# LurkerNanov12.net
KiCad netlist of a schematic drawn in EAGLE
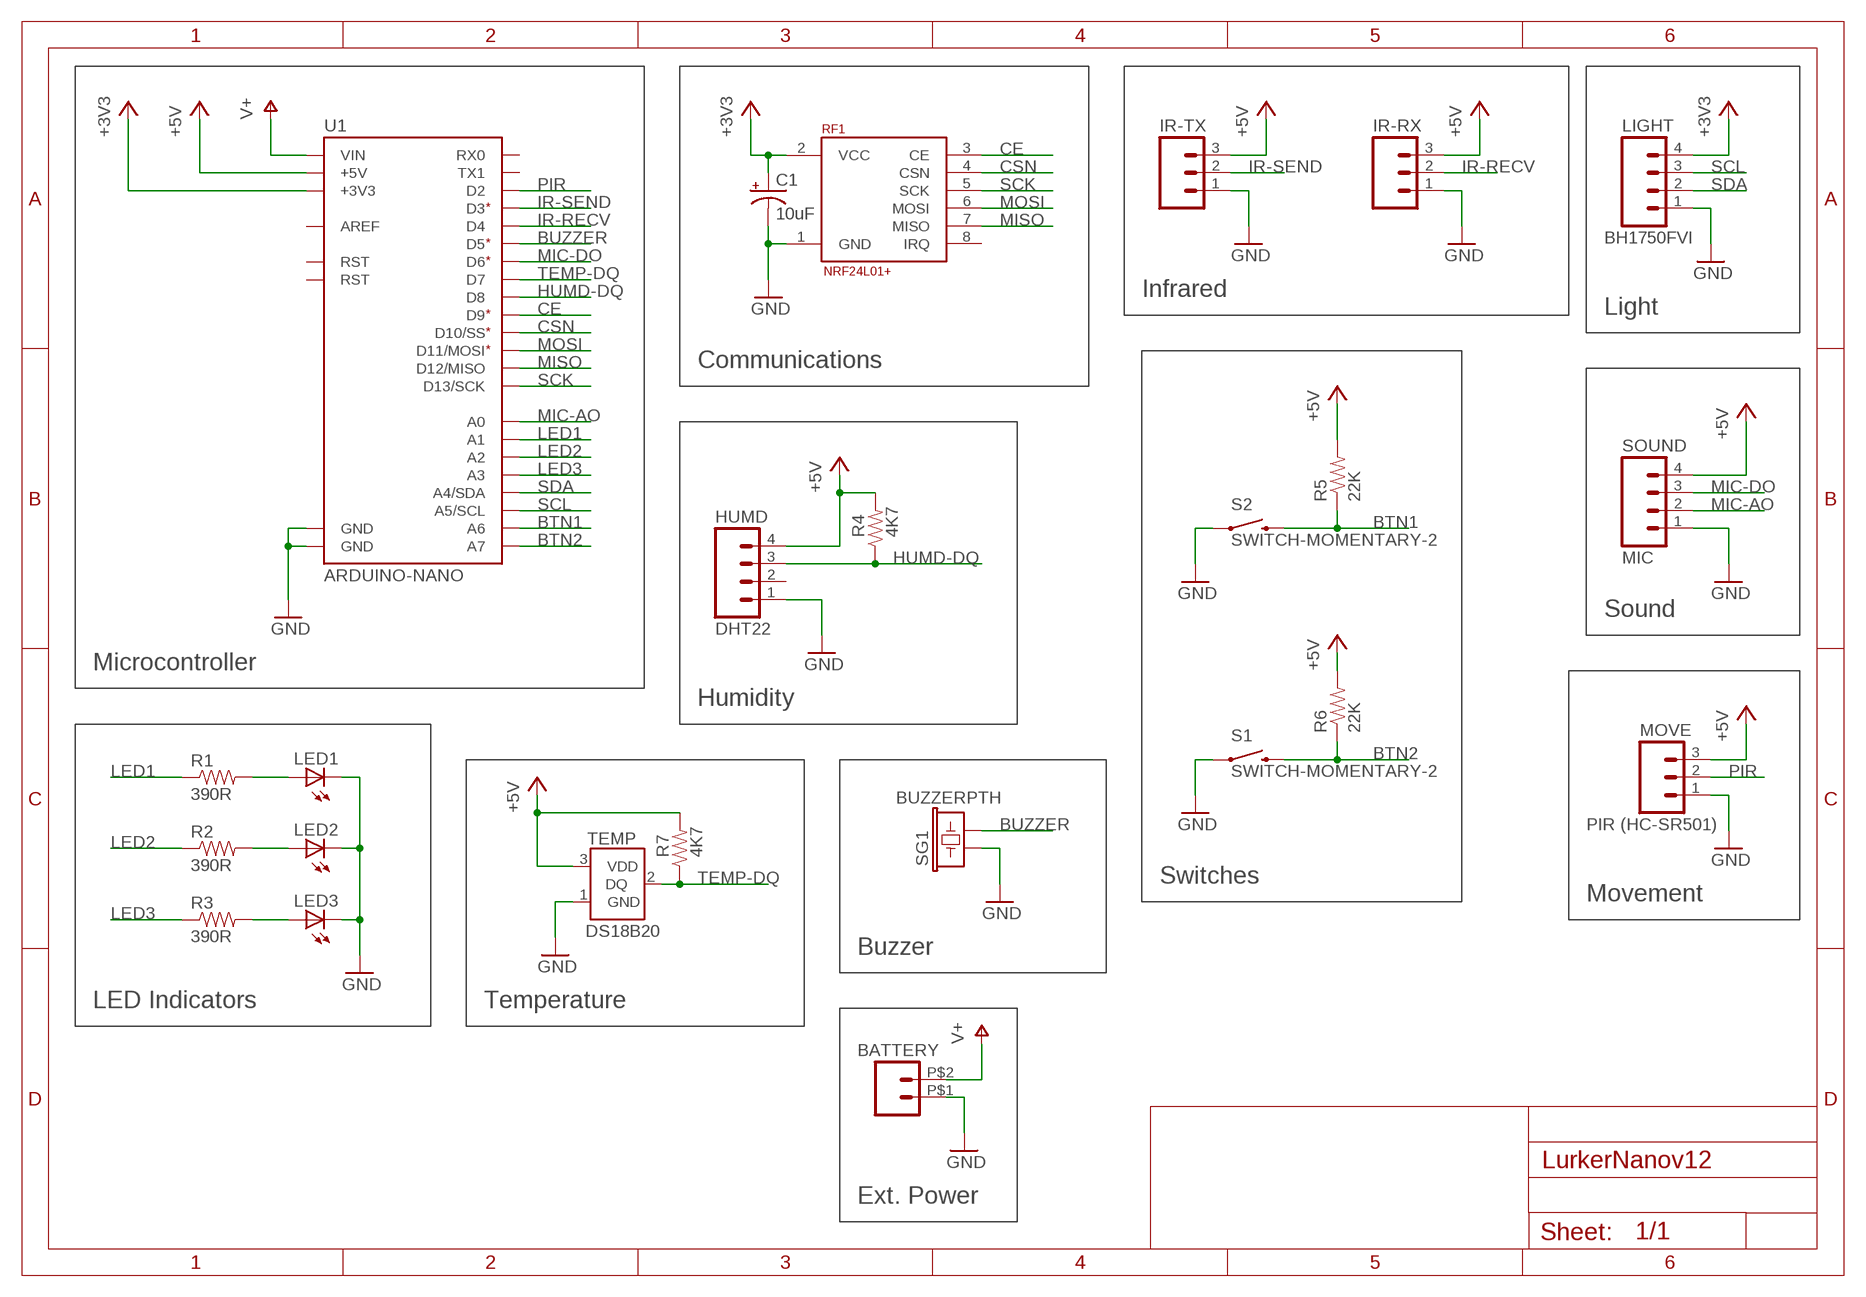
[diagram p0: schematic, sheet 1, part 1 of 2]
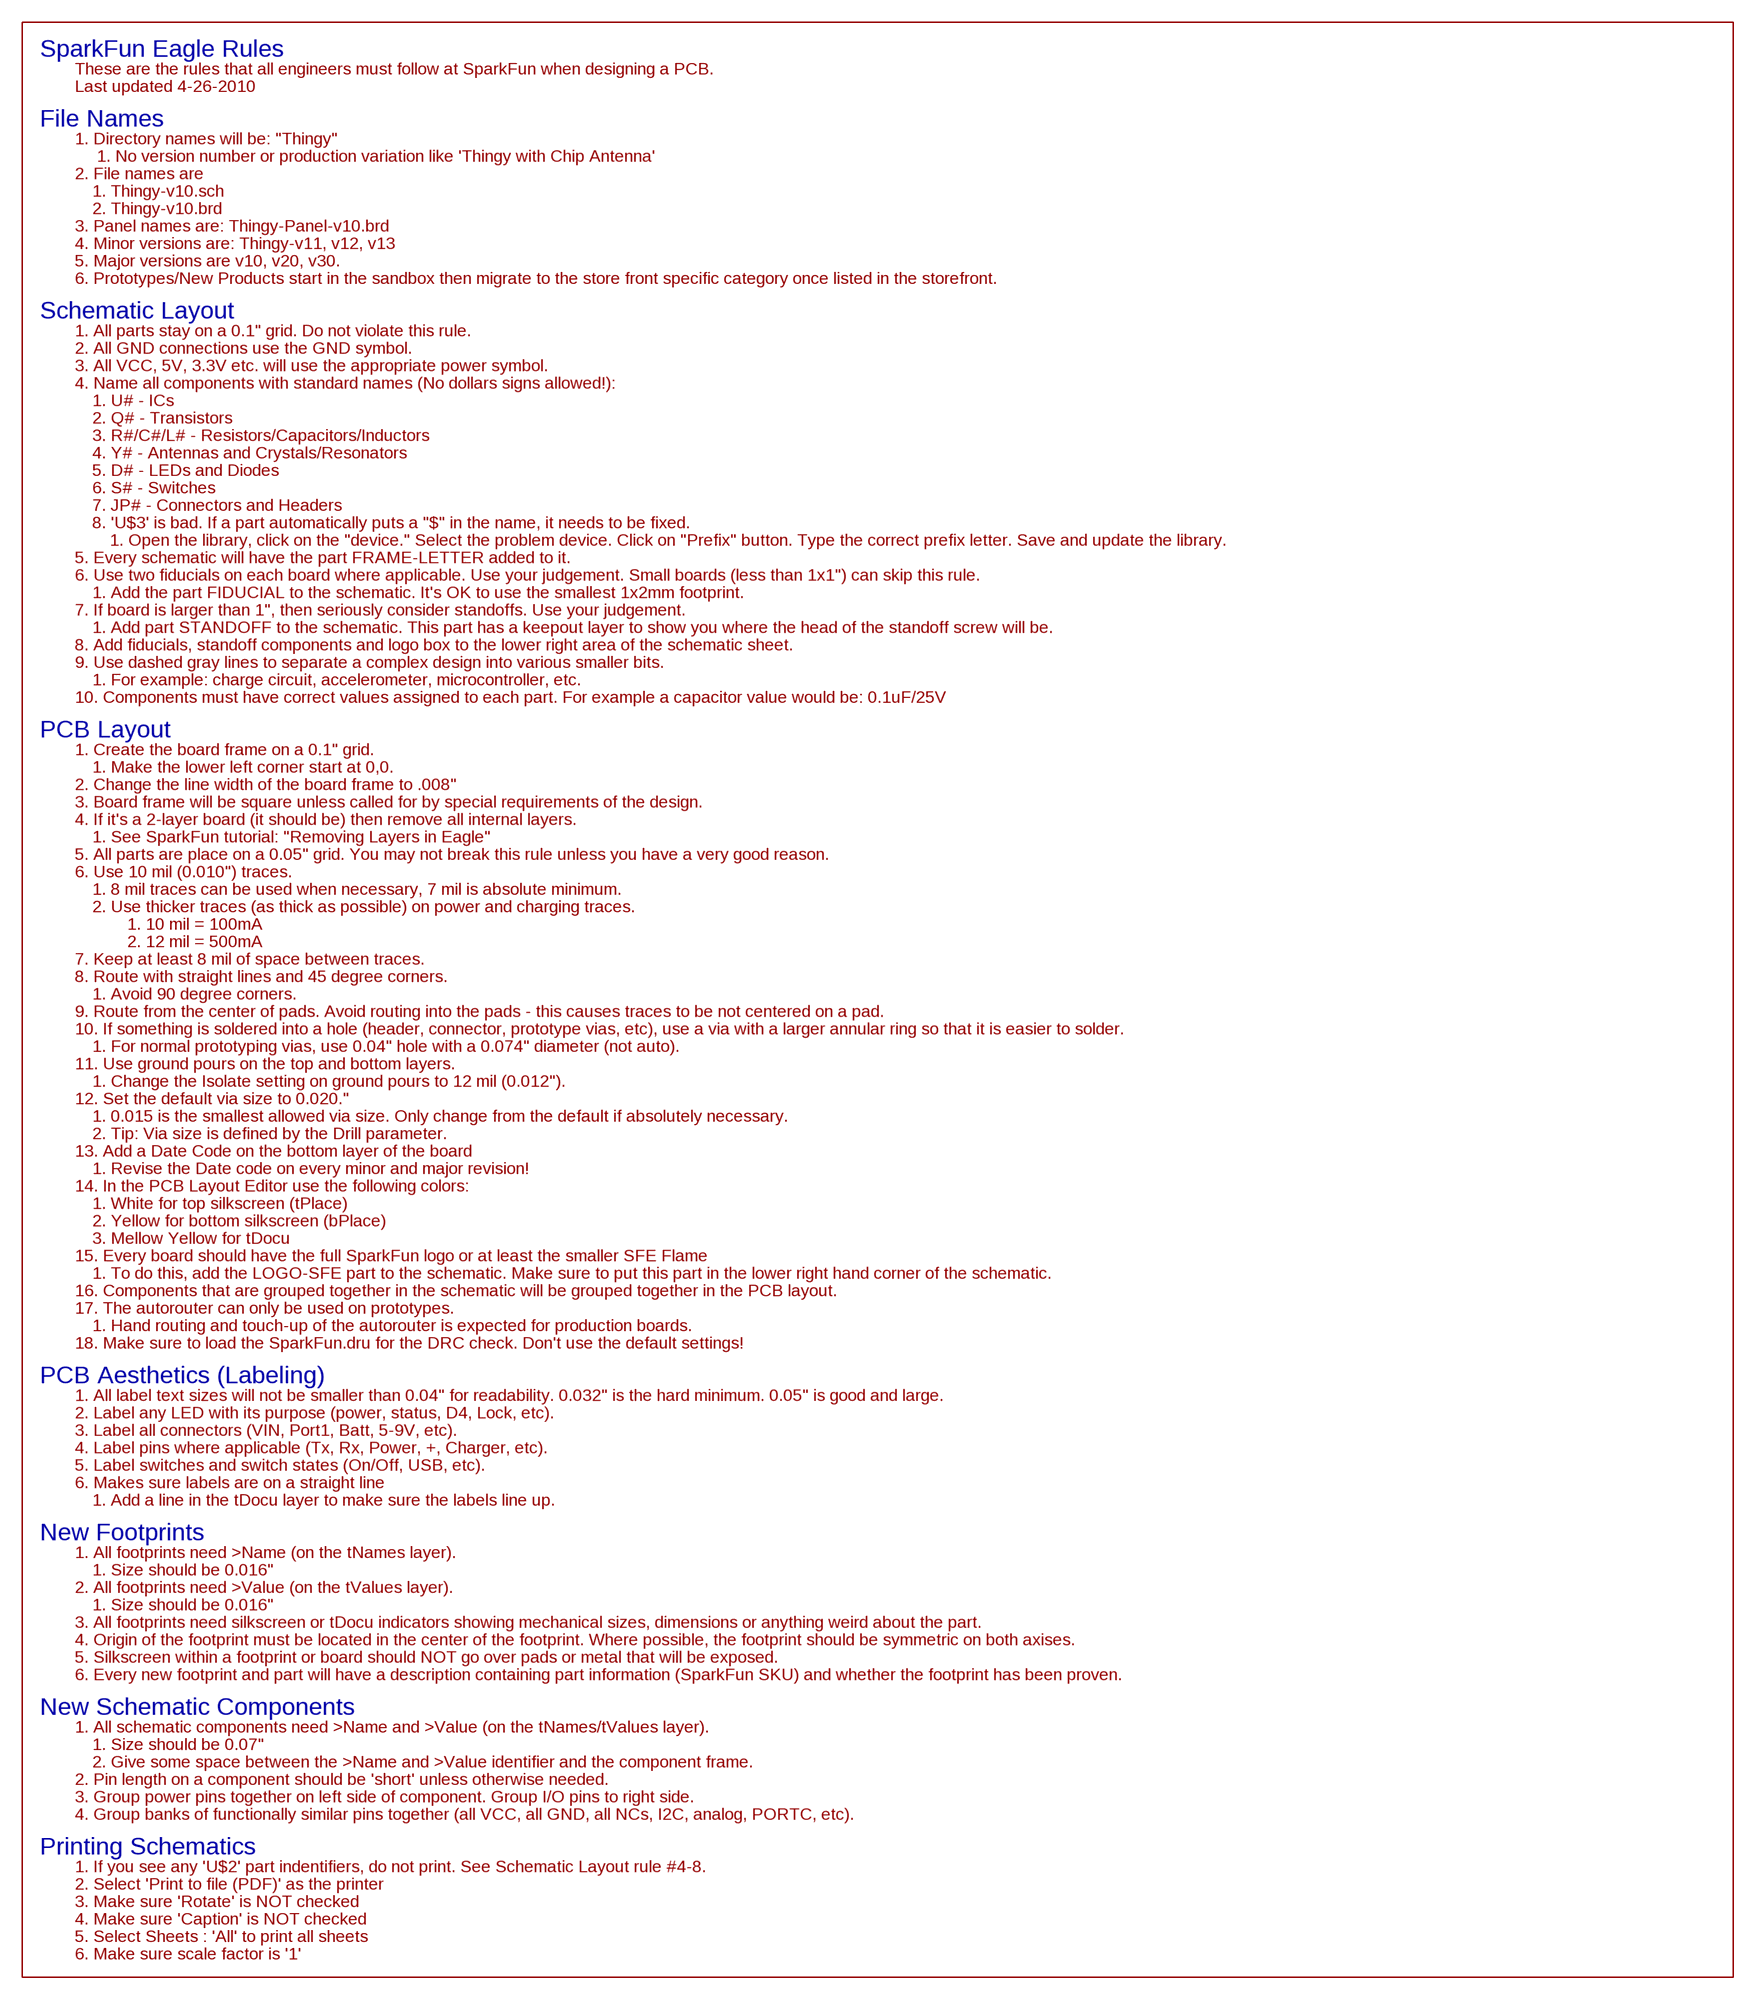
[diagram p1: schematic, sheet 1, part 2 of 2]

(export (version "E")
  (design (tool "Eeschema 10.0.6"))
  (components
    (comp (ref "BATTERY")
      (value "M02PTH2")
      (footprint "eagle-import:1X02_BIG")
      (libsource (lib "eagle-import") (part "M02PTH2"))
    )
    (comp (ref "C1")
      (value "10uF")
      (footprint "eagle-import:EIA3216")
      (libsource (lib "eagle-import") (part "CAP_POL1206"))
    )
    (comp (ref "HUMD")
      (value "DHT22")
      (footprint "eagle-import:1X04")
      (libsource (lib "eagle-import") (part "M04PTH"))
    )
    (comp (ref "IR-RX")
      (value "M03PTH")
      (footprint "eagle-import:1X03")
      (libsource (lib "eagle-import") (part "M03PTH"))
    )
    (comp (ref "IR-TX")
      (value "M03PTH")
      (footprint "eagle-import:1X03")
      (libsource (lib "eagle-import") (part "M03PTH"))
    )
    (comp (ref "LED1")
      (value "LED1206")
      (footprint "eagle-import:LED-1206")
      (libsource (lib "eagle-import") (part "LED1206"))
    )
    (comp (ref "LED2")
      (value "LED1206")
      (footprint "eagle-import:LED-1206")
      (libsource (lib "eagle-import") (part "LED1206"))
    )
    (comp (ref "LED3")
      (value "LED1206")
      (footprint "eagle-import:LED-1206")
      (libsource (lib "eagle-import") (part "LED1206"))
    )
    (comp (ref "LIGHT")
      (value "BH1750FVI")
      (footprint "eagle-import:1X04")
      (libsource (lib "eagle-import") (part "M04PTH"))
    )
    (comp (ref "MOVE")
      (value "PIR (HC-SR501)")
      (footprint "eagle-import:1X03")
      (libsource (lib "eagle-import") (part "M03PTH"))
    )
    (comp (ref "R1")
      (value "390R")
      (footprint "eagle-import:1206")
      (libsource (lib "eagle-import") (part "RESISTOR1206"))
    )
    (comp (ref "R2")
      (value "390R")
      (footprint "eagle-import:1206")
      (libsource (lib "eagle-import") (part "RESISTOR1206"))
    )
    (comp (ref "R3")
      (value "390R")
      (footprint "eagle-import:1206")
      (libsource (lib "eagle-import") (part "RESISTOR1206"))
    )
    (comp (ref "R4")
      (value "4K7")
      (footprint "eagle-import:1206")
      (libsource (lib "eagle-import") (part "RESISTOR1206"))
    )
    (comp (ref "R5")
      (value "22K")
      (footprint "eagle-import:1206")
      (libsource (lib "eagle-import") (part "RESISTOR1206"))
    )
    (comp (ref "R6")
      (value "22K")
      (footprint "eagle-import:1206")
      (libsource (lib "eagle-import") (part "RESISTOR1206"))
    )
    (comp (ref "R7")
      (value "4K7")
      (footprint "eagle-import:1206")
      (libsource (lib "eagle-import") (part "RESISTOR1206"))
    )
    (comp (ref "RF1")
      (value "NRF24L01+")
      (footprint "eagle-import:NRF24L01+-HEADER")
      (libsource (lib "eagle-import") (part "NRF24L01+"))
    )
    (comp (ref "S1")
      (value "SWITCH-MOMENTARY-2")
      (footprint "eagle-import:TACTILE_SWITCH_TALL")
      (libsource (lib "eagle-import") (part "SWITCH-MOMENTARY-2"))
    )
    (comp (ref "S2")
      (value "SWITCH-MOMENTARY-2")
      (footprint "eagle-import:TACTILE_SWITCH_TALL")
      (libsource (lib "eagle-import") (part "SWITCH-MOMENTARY-2"))
    )
    (comp (ref "SG1")
      (value "BUZZERPTH")
      (footprint "eagle-import:BUZZER-12MM")
      (libsource (lib "eagle-import") (part "BUZZERPTH"))
    )
    (comp (ref "SOUND")
      (value "MIC")
      (footprint "eagle-import:1X04")
      (libsource (lib "eagle-import") (part "M04PTH"))
    )
    (comp (ref "TEMP")
      (value "DS18B20")
      (footprint "eagle-import:TO-92-AMMO")
      (libsource (lib "eagle-import") (part "DS18B20"))
    )
    (comp (ref "U1")
      (value "ARDUINO-NANO")
      (footprint "eagle-import:NANO-SHIELD")
      (libsource (lib "eagle-import") (part "ARDUINO-NANO"))
    )
  )
  (nets
    (net (code "1") (name "+3V3") (class "Default")
      (node (ref "C1") (pin "A") (pinfunction "+_A") (pintype "passive"))
      (node (ref "LIGHT") (pin "4") (pinfunction "4_4") (pintype "passive"))
      (node (ref "RF1") (pin "2") (pinfunction "VCC_2") (pintype "power_in"))
      (node (ref "U1") (pin "3V3") (pinfunction "+3V3_3V3") (pintype "power_in"))
    )
    (net (code "2") (name "+5V") (class "Default")
      (node (ref "HUMD") (pin "4") (pinfunction "4_4") (pintype "passive"))
      (node (ref "IR-RX") (pin "3") (pinfunction "3_3") (pintype "passive"))
      (node (ref "IR-TX") (pin "3") (pinfunction "3_3") (pintype "passive"))
      (node (ref "MOVE") (pin "3") (pinfunction "3_3") (pintype "passive"))
      (node (ref "R4") (pin "2") (pinfunction "2_2") (pintype "passive"))
      (node (ref "R5") (pin "2") (pinfunction "2_2") (pintype "passive"))
      (node (ref "R6") (pin "2") (pinfunction "2_2") (pintype "passive"))
      (node (ref "R7") (pin "2") (pinfunction "2_2") (pintype "passive"))
      (node (ref "SOUND") (pin "4") (pinfunction "4_4") (pintype "passive"))
      (node (ref "TEMP") (pin "3") (pinfunction "VDD_3") (pintype "power_in"))
      (node (ref "U1") (pin "5V") (pinfunction "+5V_5V") (pintype "power_in"))
    )
    (net (code "3") (name "/BTN1") (class "Default")
      (node (ref "R5") (pin "1") (pinfunction "1_1") (pintype "passive"))
      (node (ref "S2") (pin "B2") (pinfunction "2_B2") (pintype "passive"))
      (node (ref "U1") (pin "A6") (pinfunction "A6_A6") (pintype "bidirectional"))
    )
    (net (code "4") (name "/BTN2") (class "Default")
      (node (ref "R6") (pin "1") (pinfunction "1_1") (pintype "passive"))
      (node (ref "S1") (pin "B2") (pinfunction "2_B2") (pintype "passive"))
      (node (ref "U1") (pin "A7") (pinfunction "A7_A7") (pintype "bidirectional"))
    )
    (net (code "5") (name "/BUZZER") (class "Default")
      (node (ref "SG1") (pin "-") (pinfunction "2_-") (pintype "passive"))
      (node (ref "U1") (pin "D5") (pinfunction "D5_D5") (pintype "bidirectional"))
    )
    (net (code "6") (name "/CE") (class "Default")
      (node (ref "RF1") (pin "3") (pinfunction "CE_3") (pintype "bidirectional"))
      (node (ref "U1") (pin "D9") (pinfunction "D9_D9") (pintype "bidirectional"))
    )
    (net (code "7") (name "/CSN") (class "Default")
      (node (ref "RF1") (pin "4") (pinfunction "CSN_4") (pintype "bidirectional"))
      (node (ref "U1") (pin "D10") (pinfunction "D10/SS_D10") (pintype "bidirectional"))
    )
    (net (code "8") (name "/HUMD-DQ") (class "Default")
      (node (ref "HUMD") (pin "3") (pinfunction "3_3") (pintype "passive"))
      (node (ref "R4") (pin "1") (pinfunction "1_1") (pintype "passive"))
      (node (ref "U1") (pin "D8") (pinfunction "D8_D8") (pintype "bidirectional"))
    )
    (net (code "9") (name "/IR-RECV") (class "Default")
      (node (ref "IR-RX") (pin "2") (pinfunction "2_2") (pintype "passive"))
      (node (ref "U1") (pin "D4") (pinfunction "D4_D4") (pintype "bidirectional"))
    )
    (net (code "10") (name "/IR-SEND") (class "Default")
      (node (ref "IR-TX") (pin "2") (pinfunction "2_2") (pintype "passive"))
      (node (ref "U1") (pin "D3") (pinfunction "D3_D3") (pintype "bidirectional"))
    )
    (net (code "11") (name "/LED1") (class "Default")
      (node (ref "R1") (pin "1") (pinfunction "1_1") (pintype "passive"))
      (node (ref "U1") (pin "A1") (pinfunction "A1_A1") (pintype "bidirectional"))
    )
    (net (code "12") (name "/LED2") (class "Default")
      (node (ref "R2") (pin "1") (pinfunction "1_1") (pintype "passive"))
      (node (ref "U1") (pin "A2") (pinfunction "A2_A2") (pintype "bidirectional"))
    )
    (net (code "13") (name "/LED3") (class "Default")
      (node (ref "R3") (pin "1") (pinfunction "1_1") (pintype "passive"))
      (node (ref "U1") (pin "A3") (pinfunction "A3_A3") (pintype "bidirectional"))
    )
    (net (code "14") (name "/MIC-AO") (class "Default")
      (node (ref "SOUND") (pin "2") (pinfunction "2_2") (pintype "passive"))
      (node (ref "U1") (pin "A0") (pinfunction "A0_A0") (pintype "bidirectional"))
    )
    (net (code "15") (name "/MIC-DO") (class "Default")
      (node (ref "SOUND") (pin "3") (pinfunction "3_3") (pintype "passive"))
      (node (ref "U1") (pin "D6") (pinfunction "D6_D6") (pintype "bidirectional"))
    )
    (net (code "16") (name "/MISO") (class "Default")
      (node (ref "RF1") (pin "7") (pinfunction "MISO_7") (pintype "bidirectional"))
      (node (ref "U1") (pin "D12") (pinfunction "D12/MISO_D12") (pintype "bidirectional"))
    )
    (net (code "17") (name "/MOSI") (class "Default")
      (node (ref "RF1") (pin "6") (pinfunction "MOSI_6") (pintype "bidirectional"))
      (node (ref "U1") (pin "D11") (pinfunction "D11/MOSI_D11") (pintype "bidirectional"))
    )
    (net (code "18") (name "/PIR") (class "Default")
      (node (ref "MOVE") (pin "2") (pinfunction "2_2") (pintype "passive"))
      (node (ref "U1") (pin "D2") (pinfunction "D2_D2") (pintype "bidirectional"))
    )
    (net (code "19") (name "/SCK") (class "Default")
      (node (ref "RF1") (pin "5") (pinfunction "SCK_5") (pintype "bidirectional"))
      (node (ref "U1") (pin "D13") (pinfunction "D13/SCK_D13") (pintype "bidirectional"))
    )
    (net (code "20") (name "/SCL") (class "Default")
      (node (ref "LIGHT") (pin "3") (pinfunction "3_3") (pintype "passive"))
      (node (ref "U1") (pin "A5") (pinfunction "A5/SCL_A5") (pintype "bidirectional"))
    )
    (net (code "21") (name "/SDA") (class "Default")
      (node (ref "LIGHT") (pin "2") (pinfunction "2_2") (pintype "passive"))
      (node (ref "U1") (pin "A4") (pinfunction "A4/SDA_A4") (pintype "bidirectional"))
    )
    (net (code "22") (name "/TEMP-DQ") (class "Default")
      (node (ref "R7") (pin "1") (pinfunction "1_1") (pintype "passive"))
      (node (ref "TEMP") (pin "2") (pinfunction "DQ_2") (pintype "bidirectional"))
      (node (ref "U1") (pin "D7") (pinfunction "D7_D7") (pintype "bidirectional"))
    )
    (net (code "23") (name "GND") (class "Default")
      (node (ref "BATTERY") (pin "P$1") (pinfunction "1_P$1") (pintype "passive"))
      (node (ref "C1") (pin "C") (pinfunction "-_C") (pintype "passive"))
      (node (ref "HUMD") (pin "1") (pinfunction "1_1") (pintype "passive"))
      (node (ref "IR-RX") (pin "1") (pinfunction "1_1") (pintype "passive"))
      (node (ref "IR-TX") (pin "1") (pinfunction "1_1") (pintype "passive"))
      (node (ref "LED1") (pin "C") (pinfunction "C_C") (pintype "passive"))
      (node (ref "LED2") (pin "C") (pinfunction "C_C") (pintype "passive"))
      (node (ref "LED3") (pin "C") (pinfunction "C_C") (pintype "passive"))
      (node (ref "LIGHT") (pin "1") (pinfunction "1_1") (pintype "passive"))
      (node (ref "MOVE") (pin "1") (pinfunction "1_1") (pintype "passive"))
      (node (ref "RF1") (pin "1") (pinfunction "GND_1") (pintype "power_in"))
      (node (ref "S1") (pin "A2") (pinfunction "1_A2") (pintype "passive"))
      (node (ref "S2") (pin "A2") (pinfunction "1_A2") (pintype "passive"))
      (node (ref "SG1") (pin "+") (pinfunction "1_+") (pintype "passive"))
      (node (ref "SOUND") (pin "1") (pinfunction "1_1") (pintype "passive"))
      (node (ref "TEMP") (pin "1") (pinfunction "GND_1") (pintype "power_in"))
      (node (ref "U1") (pin "GND@0") (pinfunction "GND_GND@0") (pintype "power_in"))
      (node (ref "U1") (pin "GND@1") (pinfunction "GND_GND@1") (pintype "power_in"))
    )
    (net (code "24") (name "Net-(LED1-PadA)") (class "Default")
      (node (ref "LED1") (pin "A") (pinfunction "A_A") (pintype "passive"))
      (node (ref "R1") (pin "2") (pinfunction "2_2") (pintype "passive"))
    )
    (net (code "25") (name "Net-(LED2-PadA)") (class "Default")
      (node (ref "LED2") (pin "A") (pinfunction "A_A") (pintype "passive"))
      (node (ref "R2") (pin "2") (pinfunction "2_2") (pintype "passive"))
    )
    (net (code "26") (name "Net-(LED3-PadA)") (class "Default")
      (node (ref "LED3") (pin "A") (pinfunction "A_A") (pintype "passive"))
      (node (ref "R3") (pin "2") (pinfunction "2_2") (pintype "passive"))
    )
    (net (code "27") (name "V+") (class "Default")
      (node (ref "BATTERY") (pin "P$2") (pinfunction "2_P$2") (pintype "passive"))
      (node (ref "U1") (pin "VIN") (pinfunction "VIN_VIN") (pintype "power_in"))
    )
    (net (code "28") (name "unconnected-(HUMD-Pad2)") (class "Default")
      (node (ref "HUMD") (pin "2") (pinfunction "2_2") (pintype "passive"))
    )
    (net (code "29") (name "unconnected-(RF1-IRQ-Pad8)") (class "Default")
      (node (ref "RF1") (pin "8") (pinfunction "IRQ_8") (pintype "bidirectional"))
    )
    (net (code "30") (name "unconnected-(U1-AREF-PadREF)") (class "Default")
      (node (ref "U1") (pin "REF") (pinfunction "AREF_REF") (pintype "output"))
    )
    (net (code "31") (name "unconnected-(U1-PadRST)") (class "Default")
      (node (ref "U1") (pin "RST") (pinfunction "RST_RST") (pintype "bidirectional"))
    )
    (net (code "32") (name "unconnected-(U1-RST-PadRST@0)") (class "Default")
      (node (ref "U1") (pin "RST@0") (pinfunction "RST_RST@0") (pintype "bidirectional"))
    )
    (net (code "33") (name "unconnected-(U1-RX0-PadRX)") (class "Default")
      (node (ref "U1") (pin "RX") (pinfunction "RX0_RX") (pintype "bidirectional"))
    )
    (net (code "34") (name "unconnected-(U1-TX1-PadTX)") (class "Default")
      (node (ref "U1") (pin "TX") (pinfunction "TX1_TX") (pintype "bidirectional"))
    )
  )
)
